# 2_Encoder_Interface.net
KiCad netlist of a schematic drawn in Altium Designer
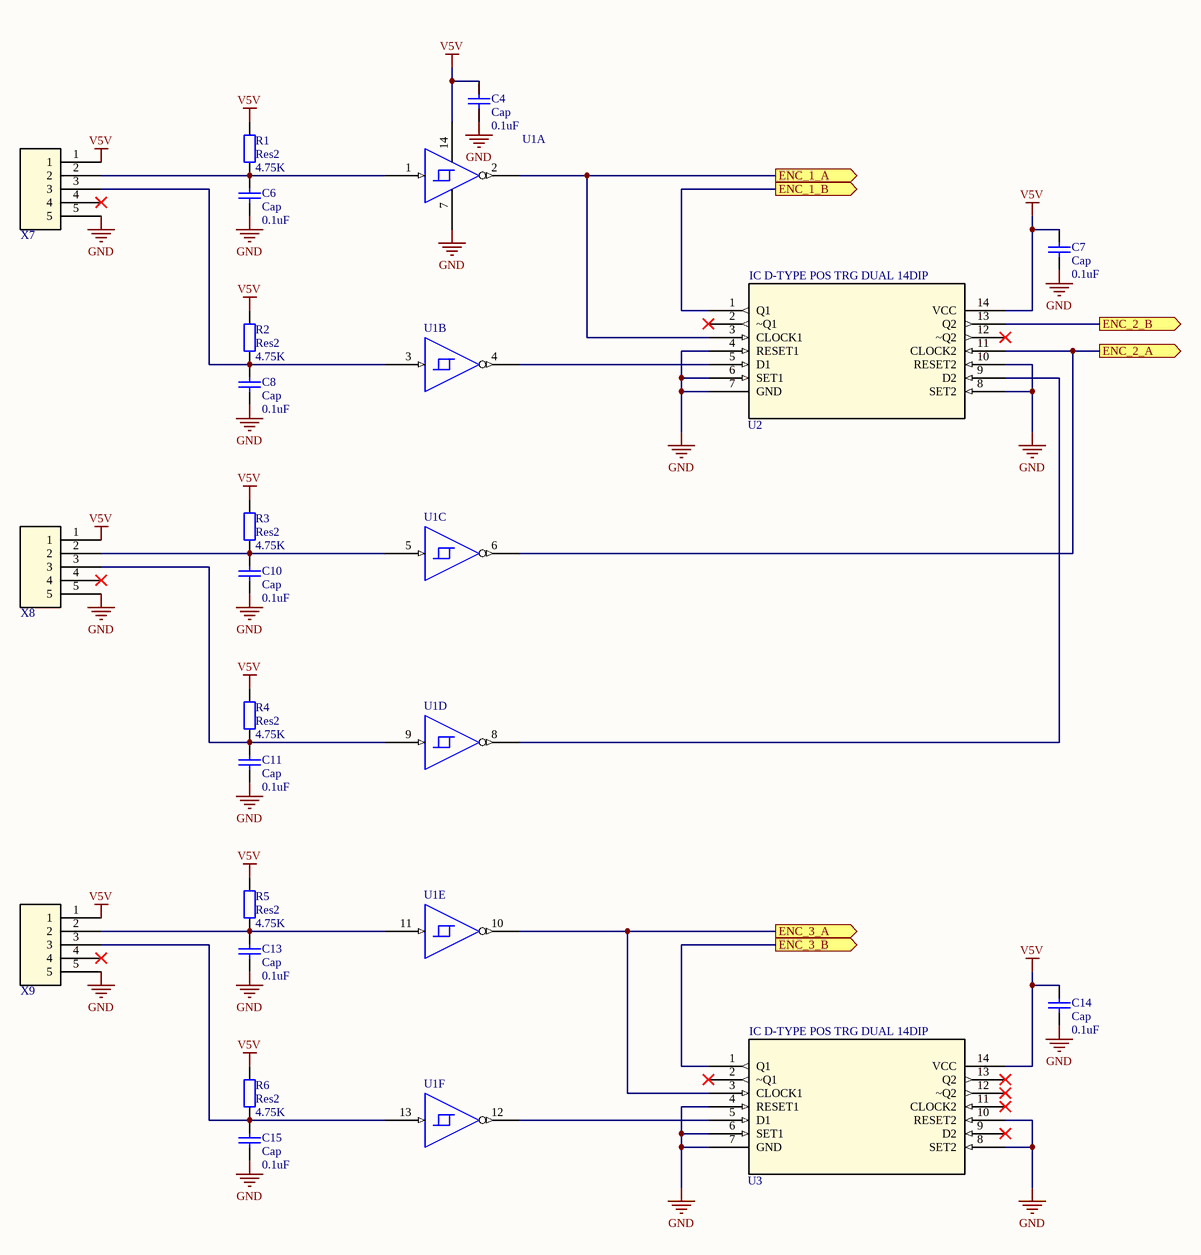
[diagram p0: 2_Encoder_Interface.SchDoc]

(export (version "E")
  (design (tool "Eeschema 10.0.6"))
  (components
    (comp (ref "C4")
      (value "Cap")
      (footprint "RAD-0.3")
      (description "Capacitor")
      (fields (field (name "ALTIUM_VALUE") "0.1uF") (field (name "PUBLISHER") "Altium Limited"))
      (libsource (lib "Miscellaneous Devices") (part "Cap"))
    )
    (comp (ref "C6")
      (value "Cap")
      (footprint "RAD-0.3")
      (description "Capacitor")
      (fields (field (name "ALTIUM_VALUE") "0.1uF") (field (name "PUBLISHER") "Altium Limited"))
      (libsource (lib "Miscellaneous Devices") (part "Cap"))
    )
    (comp (ref "C7")
      (value "Cap")
      (footprint "RAD-0.3")
      (description "Capacitor")
      (fields (field (name "ALTIUM_VALUE") "0.1uF") (field (name "PUBLISHER") "Altium Limited"))
      (libsource (lib "Miscellaneous Devices") (part "Cap"))
    )
    (comp (ref "C8")
      (value "Cap")
      (footprint "RAD-0.3")
      (description "Capacitor")
      (fields (field (name "ALTIUM_VALUE") "0.1uF") (field (name "PUBLISHER") "Altium Limited"))
      (libsource (lib "Miscellaneous Devices") (part "Cap"))
    )
    (comp (ref "C10")
      (value "Cap")
      (footprint "RAD-0.3")
      (description "Capacitor")
      (fields (field (name "ALTIUM_VALUE") "0.1uF") (field (name "PUBLISHER") "Altium Limited"))
      (libsource (lib "Miscellaneous Devices") (part "Cap"))
    )
    (comp (ref "C11")
      (value "Cap")
      (footprint "RAD-0.3")
      (description "Capacitor")
      (fields (field (name "ALTIUM_VALUE") "0.1uF") (field (name "PUBLISHER") "Altium Limited"))
      (libsource (lib "Miscellaneous Devices") (part "Cap"))
    )
    (comp (ref "C13")
      (value "Cap")
      (footprint "RAD-0.3")
      (description "Capacitor")
      (fields (field (name "ALTIUM_VALUE") "0.1uF") (field (name "PUBLISHER") "Altium Limited"))
      (libsource (lib "Miscellaneous Devices") (part "Cap"))
    )
    (comp (ref "C14")
      (value "Cap")
      (footprint "RAD-0.3")
      (description "Capacitor")
      (fields (field (name "ALTIUM_VALUE") "0.1uF") (field (name "PUBLISHER") "Altium Limited"))
      (libsource (lib "Miscellaneous Devices") (part "Cap"))
    )
    (comp (ref "C15")
      (value "Cap")
      (footprint "RAD-0.3")
      (description "Capacitor")
      (fields (field (name "ALTIUM_VALUE") "0.1uF") (field (name "PUBLISHER") "Altium Limited"))
      (libsource (lib "Miscellaneous Devices") (part "Cap"))
    )
    (comp (ref "R1")
      (value "Res2")
      (footprint "AXIAL-0.4")
      (description "Resistor")
      (fields (field (name "ALTIUM_VALUE") "4.75K") (field (name "PUBLISHER") "Altium Limited"))
      (libsource (lib "Miscellaneous Devices") (part "Res2"))
    )
    (comp (ref "R2")
      (value "Res2")
      (footprint "AXIAL-0.4")
      (description "Resistor")
      (fields (field (name "ALTIUM_VALUE") "4.75K") (field (name "PUBLISHER") "Altium Limited"))
      (libsource (lib "Miscellaneous Devices") (part "Res2"))
    )
    (comp (ref "R3")
      (value "Res2")
      (footprint "AXIAL-0.4")
      (description "Resistor")
      (fields (field (name "ALTIUM_VALUE") "4.75K") (field (name "PUBLISHER") "Altium Limited"))
      (libsource (lib "Miscellaneous Devices") (part "Res2"))
    )
    (comp (ref "R4")
      (value "Res2")
      (footprint "AXIAL-0.4")
      (description "Resistor")
      (fields (field (name "ALTIUM_VALUE") "4.75K") (field (name "PUBLISHER") "Altium Limited"))
      (libsource (lib "Miscellaneous Devices") (part "Res2"))
    )
    (comp (ref "R5")
      (value "Res2")
      (footprint "AXIAL-0.4")
      (description "Resistor")
      (fields (field (name "ALTIUM_VALUE") "4.75K") (field (name "PUBLISHER") "Altium Limited"))
      (libsource (lib "Miscellaneous Devices") (part "Res2"))
    )
    (comp (ref "R6")
      (value "Res2")
      (footprint "AXIAL-0.4")
      (description "Resistor")
      (fields (field (name "ALTIUM_VALUE") "4.75K") (field (name "PUBLISHER") "Altium Limited"))
      (libsource (lib "Miscellaneous Devices") (part "Res2"))
    )
    (comp (ref "U1")
      (value "IC HEX SCHMITT-TRIG INV 14-DIP")
      (footprint "14-DIP")
      (fields
        (field (name "DIGI-KEY_PART_NUMBER") "296-4368-5-ND")
        (field (name "MANUFACTUER_PART_NUMBER") "SN74ACT14N")
        (field (name "MANUFACTURER") "Texas Instruments")
      )
      (libsource (lib "thomas_lib") (part "IC HEX SCHMITT-TRIG INV 14-DIP"))
    )
    (comp (ref "U2")
      (value "IC D-TYPE POS TRG DUAL 14DIP")
      (footprint "thomas_lib:14-DIP")
      (fields
        (field (name "MANUFACTURER_PART_NUMBER") "CD4013BE")
        (field (name "DIGI-KEY_PART_NUMBER") "296-2033-5-ND")
        (field (name "MANUFACTURER") "Texas Instruments")
      )
      (libsource (lib "thomas_lib") (part "IC D-TYPE POS TRG DUAL 14DIP"))
    )
    (comp (ref "U3")
      (value "IC D-TYPE POS TRG DUAL 14DIP")
      (footprint "thomas_lib:14-DIP")
      (fields
        (field (name "MANUFACTURER_PART_NUMBER") "CD4013BE")
        (field (name "DIGI-KEY_PART_NUMBER") "296-2033-5-ND")
        (field (name "MANUFACTURER") "Texas Instruments")
      )
      (libsource (lib "thomas_lib") (part "IC D-TYPE POS TRG DUAL 14DIP"))
    )
    (comp (ref "X7")
      (value "TERM BLOCK HDR 5POS VERT 3.5MM")
      (footprint "WR-TBL-3211 5")
      (fields
        (field (name "DIGIKEY_PART_NUMBER") "732-2766-ND")
        (field (name "MANUFACTURER_PART_NUMBER") "691321100005")
        (field (name "MANUFACTURER") "Wurth Electronics Inc")
      )
      (libsource (lib "thomas_lib") (part "TERM BLOCK HDR 5POS VERT 3.5MM"))
    )
    (comp (ref "X8")
      (value "TERM BLOCK HDR 5POS VERT 3.5MM")
      (footprint "WR-TBL-3211 5")
      (fields
        (field (name "DIGIKEY_PART_NUMBER") "732-2766-ND")
        (field (name "MANUFACTURER_PART_NUMBER") "691321100005")
        (field (name "MANUFACTURER") "Wurth Electronics Inc")
      )
      (libsource (lib "thomas_lib") (part "TERM BLOCK HDR 5POS VERT 3.5MM"))
    )
    (comp (ref "X9")
      (value "TERM BLOCK HDR 5POS VERT 3.5MM")
      (footprint "WR-TBL-3211 5")
      (fields
        (field (name "DIGIKEY_PART_NUMBER") "732-2766-ND")
        (field (name "MANUFACTURER_PART_NUMBER") "691321100005")
        (field (name "MANUFACTURER") "Wurth Electronics Inc")
      )
      (libsource (lib "thomas_lib") (part "TERM BLOCK HDR 5POS VERT 3.5MM"))
    )
  )
  (nets
    (net (code "1") (name "/ENC_1_A") (class "Default")
      (node (ref "U1") (pin "2") (pinfunction "Y_2") (pintype "output"))
      (node (ref "U2") (pin "3") (pinfunction "CLOCK1_3") (pintype "input"))
    )
    (net (code "2") (name "/ENC_1_B") (class "Default")
      (node (ref "U2") (pin "1") (pinfunction "Q1_1") (pintype "output"))
    )
    (net (code "3") (name "/ENC_2_A") (class "Default")
      (node (ref "U1") (pin "6") (pinfunction "Y_6") (pintype "output"))
      (node (ref "U2") (pin "11") (pinfunction "CLOCK2_11") (pintype "input"))
    )
    (net (code "4") (name "/ENC_2_B") (class "Default")
      (node (ref "U2") (pin "13") (pinfunction "Q2_13") (pintype "output"))
    )
    (net (code "5") (name "/ENC_3_A") (class "Default")
      (node (ref "U1") (pin "10") (pinfunction "Y_10") (pintype "output"))
      (node (ref "U3") (pin "3") (pinfunction "CLOCK1_3") (pintype "input"))
    )
    (net (code "6") (name "/ENC_3_B") (class "Default")
      (node (ref "U3") (pin "1") (pinfunction "Q1_1") (pintype "output"))
    )
    (net (code "7") (name "GND") (class "Default")
      (node (ref "C10") (pin "1") (pinfunction "1_1") (pintype "passive"))
      (node (ref "C11") (pin "1") (pinfunction "1_1") (pintype "passive"))
      (node (ref "C13") (pin "1") (pinfunction "1_1") (pintype "passive"))
      (node (ref "C14") (pin "1") (pinfunction "1_1") (pintype "passive"))
      (node (ref "C15") (pin "1") (pinfunction "1_1") (pintype "passive"))
      (node (ref "C4") (pin "1") (pinfunction "1_1") (pintype "passive"))
      (node (ref "C6") (pin "1") (pinfunction "1_1") (pintype "passive"))
      (node (ref "C7") (pin "1") (pinfunction "1_1") (pintype "passive"))
      (node (ref "C8") (pin "1") (pinfunction "1_1") (pintype "passive"))
      (node (ref "U1") (pin "7") (pinfunction "GND_POWER_7") (pintype "power_in"))
      (node (ref "U2") (pin "10") (pinfunction "RESET2_10") (pintype "input"))
      (node (ref "U2") (pin "4") (pinfunction "RESET1_4") (pintype "input"))
      (node (ref "U2") (pin "6") (pinfunction "SET1_6") (pintype "input"))
      (node (ref "U2") (pin "7") (pinfunction "GND_7") (pintype "power_in"))
      (node (ref "U2") (pin "8") (pinfunction "SET2_8") (pintype "input"))
      (node (ref "U3") (pin "10") (pinfunction "RESET2_10") (pintype "input"))
      (node (ref "U3") (pin "4") (pinfunction "RESET1_4") (pintype "input"))
      (node (ref "U3") (pin "6") (pinfunction "SET1_6") (pintype "input"))
      (node (ref "U3") (pin "7") (pinfunction "GND_7") (pintype "power_in"))
      (node (ref "U3") (pin "8") (pinfunction "SET2_8") (pintype "input"))
      (node (ref "X7") (pin "5") (pinfunction "5_5") (pintype "passive"))
      (node (ref "X8") (pin "5") (pinfunction "5_5") (pintype "passive"))
      (node (ref "X9") (pin "5") (pinfunction "5_5") (pintype "passive"))
    )
    (net (code "8") (name "Net-(U1A-A)") (class "Default")
      (node (ref "C6") (pin "2") (pinfunction "2_2") (pintype "passive"))
      (node (ref "R1") (pin "1") (pinfunction "1_1") (pintype "passive"))
      (node (ref "U1") (pin "1") (pinfunction "A_1") (pintype "input"))
      (node (ref "X7") (pin "2") (pinfunction "2_2") (pintype "passive"))
    )
    (net (code "9") (name "Net-(U1B-A)") (class "Default")
      (node (ref "C8") (pin "2") (pinfunction "2_2") (pintype "passive"))
      (node (ref "R2") (pin "1") (pinfunction "1_1") (pintype "passive"))
      (node (ref "U1") (pin "3") (pinfunction "A_3") (pintype "input"))
      (node (ref "X7") (pin "3") (pinfunction "3_3") (pintype "passive"))
    )
    (net (code "10") (name "Net-(U1B-Y)") (class "Default")
      (node (ref "U1") (pin "4") (pinfunction "Y_4") (pintype "output"))
      (node (ref "U2") (pin "5") (pinfunction "D1_5") (pintype "input"))
    )
    (net (code "11") (name "Net-(U1C-A)") (class "Default")
      (node (ref "C10") (pin "2") (pinfunction "2_2") (pintype "passive"))
      (node (ref "R3") (pin "1") (pinfunction "1_1") (pintype "passive"))
      (node (ref "U1") (pin "5") (pinfunction "A_5") (pintype "input"))
      (node (ref "X8") (pin "2") (pinfunction "2_2") (pintype "passive"))
    )
    (net (code "12") (name "Net-(U1D-A)") (class "Default")
      (node (ref "C11") (pin "2") (pinfunction "2_2") (pintype "passive"))
      (node (ref "R4") (pin "1") (pinfunction "1_1") (pintype "passive"))
      (node (ref "U1") (pin "9") (pinfunction "A_9") (pintype "input"))
      (node (ref "X8") (pin "3") (pinfunction "3_3") (pintype "passive"))
    )
    (net (code "13") (name "Net-(U1D-Y)") (class "Default")
      (node (ref "U1") (pin "8") (pinfunction "Y_8") (pintype "output"))
      (node (ref "U2") (pin "9") (pinfunction "D2_9") (pintype "input"))
    )
    (net (code "14") (name "Net-(U1E-A)") (class "Default")
      (node (ref "C13") (pin "2") (pinfunction "2_2") (pintype "passive"))
      (node (ref "R5") (pin "1") (pinfunction "1_1") (pintype "passive"))
      (node (ref "U1") (pin "11") (pinfunction "A_11") (pintype "input"))
      (node (ref "X9") (pin "2") (pinfunction "2_2") (pintype "passive"))
    )
    (net (code "15") (name "Net-(U1F-A)") (class "Default")
      (node (ref "C15") (pin "2") (pinfunction "2_2") (pintype "passive"))
      (node (ref "R6") (pin "1") (pinfunction "1_1") (pintype "passive"))
      (node (ref "U1") (pin "13") (pinfunction "A_13") (pintype "input"))
      (node (ref "X9") (pin "3") (pinfunction "3_3") (pintype "passive"))
    )
    (net (code "16") (name "Net-(U1F-Y)") (class "Default")
      (node (ref "U1") (pin "12") (pinfunction "Y_12") (pintype "output"))
      (node (ref "U3") (pin "5") (pinfunction "D1_5") (pintype "input"))
    )
    (net (code "17") (name "V5V") (class "Default")
      (node (ref "C14") (pin "2") (pinfunction "2_2") (pintype "passive"))
      (node (ref "C4") (pin "2") (pinfunction "2_2") (pintype "passive"))
      (node (ref "C7") (pin "2") (pinfunction "2_2") (pintype "passive"))
      (node (ref "R1") (pin "2") (pinfunction "2_2") (pintype "passive"))
      (node (ref "R2") (pin "2") (pinfunction "2_2") (pintype "passive"))
      (node (ref "R3") (pin "2") (pinfunction "2_2") (pintype "passive"))
      (node (ref "R4") (pin "2") (pinfunction "2_2") (pintype "passive"))
      (node (ref "R5") (pin "2") (pinfunction "2_2") (pintype "passive"))
      (node (ref "R6") (pin "2") (pinfunction "2_2") (pintype "passive"))
      (node (ref "U1") (pin "14") (pinfunction "VCC_14") (pintype "power_in"))
      (node (ref "U2") (pin "14") (pinfunction "VCC_14") (pintype "power_in"))
      (node (ref "U3") (pin "14") (pinfunction "VCC_14") (pintype "power_in"))
      (node (ref "X7") (pin "1") (pinfunction "1_1") (pintype "passive"))
      (node (ref "X8") (pin "1") (pinfunction "1_1") (pintype "passive"))
      (node (ref "X9") (pin "1") (pinfunction "1_1") (pintype "passive"))
    )
    (net (code "18") (name "unconnected-(U2-~Q1-Pad2)") (class "Default")
      (node (ref "U2") (pin "2") (pinfunction "~Q1_2") (pintype "output+no_connect"))
    )
    (net (code "19") (name "unconnected-(U2-~Q2-Pad12)") (class "Default")
      (node (ref "U2") (pin "12") (pinfunction "~Q2_12") (pintype "output+no_connect"))
    )
    (net (code "20") (name "unconnected-(U3-CLOCK2-Pad11)") (class "Default")
      (node (ref "U3") (pin "11") (pinfunction "CLOCK2_11") (pintype "input+no_connect"))
    )
    (net (code "21") (name "unconnected-(U3-D2-Pad9)") (class "Default")
      (node (ref "U3") (pin "9") (pinfunction "D2_9") (pintype "input+no_connect"))
    )
    (net (code "22") (name "unconnected-(U3-Q2-Pad13)") (class "Default")
      (node (ref "U3") (pin "13") (pinfunction "Q2_13") (pintype "output+no_connect"))
    )
    (net (code "23") (name "unconnected-(U3-~Q1-Pad2)") (class "Default")
      (node (ref "U3") (pin "2") (pinfunction "~Q1_2") (pintype "output+no_connect"))
    )
    (net (code "24") (name "unconnected-(U3-~Q2-Pad12)") (class "Default")
      (node (ref "U3") (pin "12") (pinfunction "~Q2_12") (pintype "output+no_connect"))
    )
    (net (code "25") (name "unconnected-(X7-Pad4)") (class "Default")
      (node (ref "X7") (pin "4") (pinfunction "4_4") (pintype "passive+no_connect"))
    )
    (net (code "26") (name "unconnected-(X8-Pad4)") (class "Default")
      (node (ref "X8") (pin "4") (pinfunction "4_4") (pintype "passive+no_connect"))
    )
    (net (code "27") (name "unconnected-(X9-Pad4)") (class "Default")
      (node (ref "X9") (pin "4") (pinfunction "4_4") (pintype "passive+no_connect"))
    )
  )
)
